# Actuators.net
KiCad netlist of a schematic drawn in Altium Designer
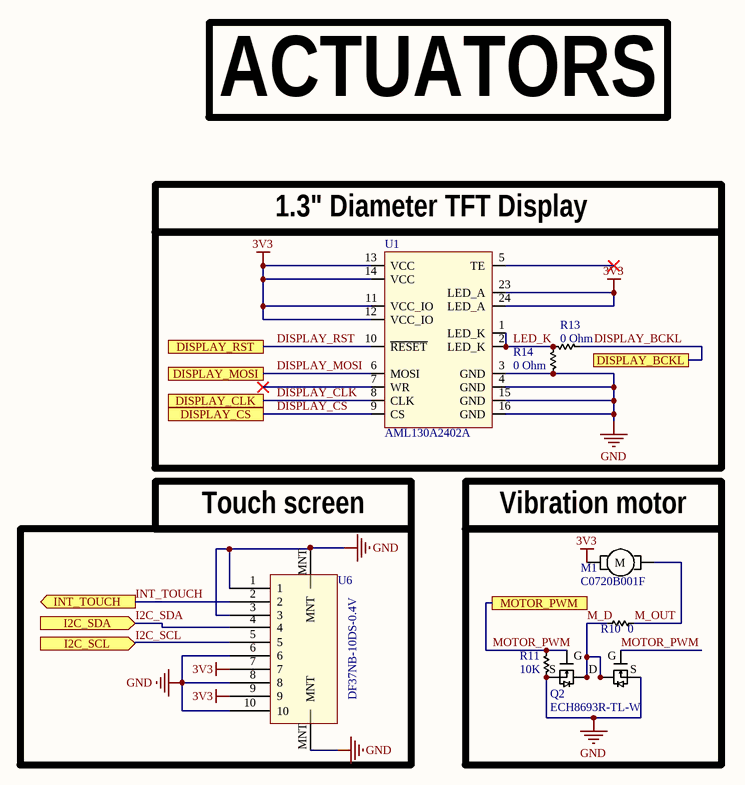
[diagram p0: Actuators.SchDoc]

(export (version "E")
  (design (tool "Eeschema 10.0.6"))
  (components
    (comp (ref "M1")
      (value "C0720B001F")
      (footprint "C0720B001F")
      (description "DC Motor Vibration, ERM 10000 RPM 3VDC")
      (libsource (lib "smLib") (part "C0720B001F"))
    )
    (comp (ref "Q2")
      (value "ECH8693R-TL-W")
      (footprint "ECH8693R-TL-W")
      (description "Mosfet Array 2 N-Channel (Dual) Common Drain 24V 14A 1.4W Surface Mount SOT-28FL/ECH8")
      (libsource (lib "smLib") (part "ECH8693R-TL-W"))
    )
    (comp (ref "R10")
      (value "0")
      (footprint "RES_0603_HIGH")
      (description "0603 Resistor")
      (libsource (lib "smLib") (part "Resistor_0603"))
    )
    (comp (ref "R11")
      (value "10K")
      (footprint "RES_0603_HIGH")
      (description "0603 Resistor")
      (libsource (lib "smLib") (part "Resistor_0603"))
    )
    (comp (ref "R13")
      (value "0 Ohm")
      (footprint "RES_0603_HIGH")
      (description "0603 Resistor")
      (libsource (lib "smLib") (part "Resistor_0603"))
    )
    (comp (ref "R14")
      (value "0 Ohm")
      (footprint "RES_0603_HIGH")
      (description "0603 Resistor")
      (libsource (lib "smLib") (part "Resistor_0603"))
    )
    (comp (ref "U1")
      (value "AML130A2402A")
      (footprint "AML130A2402A")
      (description "AML130A2402A Round 1.3\" TFT Display")
      (libsource (lib "smLib") (part "AML130A2402A"))
    )
    (comp (ref "U6")
      (value "DF37NB-10DS-0.4V")
      (footprint "DF37NB-10DS-0.4V")
      (libsource (lib "Cty1") (part "DF37NB-10DS-0.4V"))
    )
  )
  (nets
    (net (code "1") (name "/DISPLAY_BCKL") (class "Default")
      (node (ref "R13") (pin "1") (pinfunction "1_1") (pintype "passive"))
    )
    (net (code "2") (name "/DISPLAY_CLK") (class "Default")
      (node (ref "U1") (pin "8") (pinfunction "CLK_8") (pintype "passive"))
    )
    (net (code "3") (name "/DISPLAY_CS") (class "Default")
      (node (ref "U1") (pin "9") (pinfunction "CS_9") (pintype "passive"))
    )
    (net (code "4") (name "/DISPLAY_MOSI") (class "Default")
      (node (ref "U1") (pin "6") (pinfunction "MOSI_6") (pintype "passive"))
    )
    (net (code "5") (name "/DISPLAY_RST") (class "Default")
      (node (ref "U1") (pin "10") (pinfunction "~{RESET}_10") (pintype "passive"))
    )
    (net (code "6") (name "/I2C_SCL") (class "Default")
      (node (ref "U6") (pin "5") (pinfunction "5_5") (pintype "passive"))
    )
    (net (code "7") (name "/I2C_SDA") (class "Default")
      (node (ref "U6") (pin "4") (pinfunction "4_4") (pintype "passive"))
    )
    (net (code "8") (name "/INT_TOUCH") (class "Default")
      (node (ref "U6") (pin "2") (pinfunction "2_2") (pintype "passive"))
    )
    (net (code "9") (name "/LED_K") (class "Default")
      (node (ref "R13") (pin "2") (pinfunction "2_2") (pintype "passive"))
      (node (ref "R14") (pin "1") (pinfunction "1_1") (pintype "passive"))
      (node (ref "U1") (pin "1") (pinfunction "LED_K_1") (pintype "passive"))
      (node (ref "U1") (pin "2") (pinfunction "LED_K_2") (pintype "passive"))
    )
    (net (code "10") (name "/MOTOR_PWM") (class "Default")
      (node (ref "Q2") (pin "2") (pinfunction "G1_2") (pintype "passive"))
      (node (ref "Q2") (pin "4") (pinfunction "G2_4") (pintype "passive"))
      (node (ref "R11") (pin "2") (pinfunction "2_2") (pintype "passive"))
    )
    (net (code "11") (name "/M_D") (class "Default")
      (node (ref "Q2") (pin "5") (pinfunction "D_5") (pintype "passive"))
      (node (ref "Q2") (pin "6") (pinfunction "D_6") (pintype "passive"))
      (node (ref "Q2") (pin "7") (pinfunction "D_7") (pintype "passive"))
      (node (ref "Q2") (pin "8") (pinfunction "D_8") (pintype "passive"))
      (node (ref "R10") (pin "1") (pinfunction "1_1") (pintype "passive"))
    )
    (net (code "12") (name "/M_OUT") (class "Default")
      (node (ref "M1") (pin "2") (pinfunction "2_2") (pintype "passive"))
      (node (ref "R10") (pin "2") (pinfunction "2_2") (pintype "passive"))
    )
    (net (code "13") (name "3V3") (class "Default")
      (node (ref "M1") (pin "1") (pinfunction "1_1") (pintype "passive"))
      (node (ref "U1") (pin "11") (pinfunction "VCC_IO_11") (pintype "passive"))
      (node (ref "U1") (pin "12") (pinfunction "VCC_IO_12") (pintype "passive"))
      (node (ref "U1") (pin "13") (pinfunction "VCC_13") (pintype "passive"))
      (node (ref "U1") (pin "14") (pinfunction "VCC_14") (pintype "passive"))
      (node (ref "U1") (pin "23") (pinfunction "LED_A_23") (pintype "passive"))
      (node (ref "U1") (pin "24") (pinfunction "LED_A_24") (pintype "passive"))
      (node (ref "U6") (pin "7") (pinfunction "7_7") (pintype "passive"))
      (node (ref "U6") (pin "9") (pinfunction "9_9") (pintype "passive"))
    )
    (net (code "14") (name "GND") (class "Default")
      (node (ref "Q2") (pin "1") (pinfunction "S1_1") (pintype "passive"))
      (node (ref "Q2") (pin "3") (pinfunction "S2_3") (pintype "passive"))
      (node (ref "R11") (pin "1") (pinfunction "1_1") (pintype "passive"))
      (node (ref "R14") (pin "2") (pinfunction "2_2") (pintype "passive"))
      (node (ref "U1") (pin "15") (pinfunction "GND_15") (pintype "passive"))
      (node (ref "U1") (pin "16") (pinfunction "GND_16") (pintype "passive"))
      (node (ref "U1") (pin "3") (pinfunction "GND_3") (pintype "passive"))
      (node (ref "U1") (pin "4") (pinfunction "GND_4") (pintype "passive"))
      (node (ref "U6") (pin "1") (pinfunction "1_1") (pintype "passive"))
      (node (ref "U6") (pin "10") (pinfunction "10_10") (pintype "passive"))
      (node (ref "U6") (pin "3") (pinfunction "3_3") (pintype "passive"))
      (node (ref "U6") (pin "6") (pinfunction "6_6") (pintype "passive"))
      (node (ref "U6") (pin "8") (pinfunction "8_8") (pintype "passive"))
      (node (ref "U6") (pin "MNT") (pinfunction "MNT_MNT") (pintype "passive"))
    )
    (net (code "15") (name "unconnected-(U1-TE-Pad5)") (class "Default")
      (node (ref "U1") (pin "5") (pinfunction "TE_5") (pintype "passive+no_connect"))
    )
    (net (code "16") (name "unconnected-(U1-WR-Pad7)") (class "Default")
      (node (ref "U1") (pin "7") (pinfunction "WR_7") (pintype "passive+no_connect"))
    )
  )
)
